# mini_metrix_clock.net
KiCad netlist of a schematic drawn in EAGLE
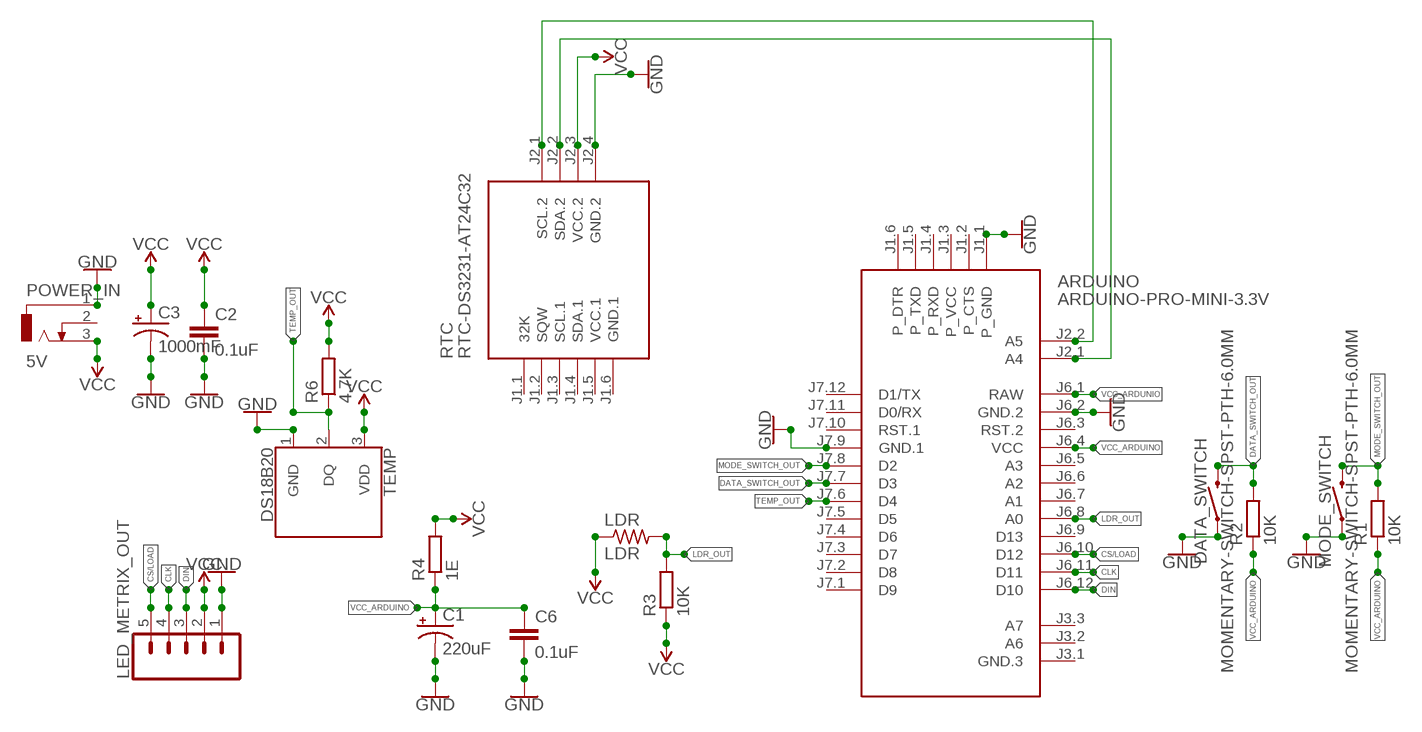
[diagram p0: schematic, sheet 1]

(export (version "E")
  (design (tool "Eeschema 10.0.6"))
  (components
    (comp (ref "ARDUINO")
      (value "ARDUINO-PRO-MINI-3.3V")
      (footprint "eagle-import:ARDUINO-PRO-MINI")
      (libsource (lib "eagle-import") (part "ARDUINO-PRO-MINI-3.3V"))
    )
    (comp (ref "C1")
      (value "220uF")
      (footprint "eagle-import:CPOL-RADIAL-2.5MM-6.5MM")
      (libsource (lib "eagle-import") (part "100UF-POLAR-RADIAL-2.5MM-25V-20%"))
    )
    (comp (ref "C2")
      (value "0.1uF")
      (footprint "eagle-import:CAP-PTH-SMALL-KIT")
      (libsource (lib "eagle-import") (part "0.1UF-KIT-EZ-50V-20%"))
    )
    (comp (ref "C3")
      (value "1000mF")
      (footprint "eagle-import:CPOL-RADIAL-5MM-10MM")
      (libsource (lib "eagle-import") (part "1000UF-RADIAL-5MM-25V-20%"))
    )
    (comp (ref "C6")
      (value "0.1uF")
      (footprint "eagle-import:CAP-PTH-SMALL-KIT")
      (libsource (lib "eagle-import") (part "0.1UF-KIT-EZ-50V-20%"))
    )
    (comp (ref "DATA_SWITCH")
      (value "MOMENTARY-SWITCH-SPST-PTH-6.0MM")
      (footprint "eagle-import:TACTILE_SWITCH_PTH_6.0MM")
      (libsource (lib "eagle-import") (part "MOMENTARY-SWITCH-SPST-PTH-6.0MM"))
    )
    (comp (ref "LDR")
      (value "LDR")
      (footprint "eagle-import:0204V")
      (libsource (lib "eagle-import") (part "R-US_0204/2V"))
    )
    (comp (ref "LED_METRIX_OUT")
      (value "CONN_05PTH_LONGPADS")
      (footprint "eagle-import:1X05_LONGPADS")
      (libsource (lib "eagle-import") (part "CONN_05PTH_LONGPADS"))
    )
    (comp (ref "MODE_SWITCH")
      (value "MOMENTARY-SWITCH-SPST-PTH-6.0MM")
      (footprint "eagle-import:TACTILE_SWITCH_PTH_6.0MM")
      (libsource (lib "eagle-import") (part "MOMENTARY-SWITCH-SPST-PTH-6.0MM"))
    )
    (comp (ref "POWER_IN")
      (value "5V")
      (footprint "eagle-import:DCJ0303")
      (libsource (lib "eagle-import") (part "DCJ0303"))
    )
    (comp (ref "R1")
      (value "10K")
      (footprint "eagle-import:0207_7")
      (libsource (lib "eagle-import") (part "R-EU_0207/7"))
    )
    (comp (ref "R2")
      (value "10K")
      (footprint "eagle-import:0207_7")
      (libsource (lib "eagle-import") (part "R-EU_0207/7"))
    )
    (comp (ref "R3")
      (value "10K")
      (footprint "eagle-import:0207_7")
      (libsource (lib "eagle-import") (part "R-EU_0207/7"))
    )
    (comp (ref "R4")
      (value "1E")
      (footprint "eagle-import:0207_7")
      (libsource (lib "eagle-import") (part "R-EU_0207/7"))
    )
    (comp (ref "R6")
      (value "4.7K")
      (footprint "eagle-import:0207_7")
      (libsource (lib "eagle-import") (part "R-EU_0207/7"))
    )
    (comp (ref "RTC")
      (value "RTC-DS3231-AT24C32")
      (footprint "eagle-import:RTC-DS3231-AT24C32")
      (libsource (lib "eagle-import") (part "RTC-DS3231-AT24C32"))
    )
    (comp (ref "TEMP")
      (value "DS18B20")
      (footprint "eagle-import:TO-92-AMMO")
      (libsource (lib "eagle-import") (part "DS18B20"))
    )
  )
  (nets
    (net (code "1") (name "/GND.1") (class "Default")
      (node (ref "RTC") (pin "J1.6") (pinfunction "GND.1_J1.6") (pintype "power_in"))
    )
    (net (code "2") (name "/VCC.1") (class "Default")
      (node (ref "RTC") (pin "J1.5") (pinfunction "VCC.1_J1.5") (pintype "power_in"))
    )
    (net (code "3") (name "CLK") (class "Default")
      (node (ref "ARDUINO") (pin "J6.11") (pinfunction "D11_J6.11") (pintype "bidirectional"))
      (node (ref "LED_METRIX_OUT") (pin "4") (pinfunction "4_4") (pintype "passive"))
    )
    (net (code "4") (name "CS{slash}LOAD") (class "Default")
      (node (ref "ARDUINO") (pin "J6.10") (pinfunction "D12_J6.10") (pintype "bidirectional"))
      (node (ref "LED_METRIX_OUT") (pin "5") (pinfunction "5_5") (pintype "passive"))
    )
    (net (code "5") (name "DATA_SWITCH_OUT") (class "Default")
      (node (ref "ARDUINO") (pin "J7.7") (pinfunction "D3_J7.7") (pintype "bidirectional"))
      (node (ref "DATA_SWITCH") (pin "3") (pinfunction "2_3") (pintype "passive"))
      (node (ref "R2") (pin "2") (pinfunction "2_2") (pintype "passive"))
    )
    (net (code "6") (name "DIN") (class "Default")
      (node (ref "ARDUINO") (pin "J6.12") (pinfunction "D10_J6.12") (pintype "bidirectional"))
      (node (ref "LED_METRIX_OUT") (pin "3") (pinfunction "3_3") (pintype "passive"))
    )
    (net (code "7") (name "GND") (class "Default")
      (node (ref "ARDUINO") (pin "J1.1") (pinfunction "P_GND_J1.1") (pintype "bidirectional"))
      (node (ref "ARDUINO") (pin "J6.2") (pinfunction "GND.2_J6.2") (pintype "power_in"))
      (node (ref "ARDUINO") (pin "J7.9") (pinfunction "GND.1_J7.9") (pintype "power_in"))
      (node (ref "C1") (pin "2") (pinfunction "-_2") (pintype "passive"))
      (node (ref "C2") (pin "2") (pinfunction "2_2") (pintype "passive"))
      (node (ref "C3") (pin "-") (pinfunction "-_-") (pintype "passive"))
      (node (ref "C6") (pin "2") (pinfunction "2_2") (pintype "passive"))
      (node (ref "DATA_SWITCH") (pin "1") (pinfunction "1_1") (pintype "passive"))
      (node (ref "LED_METRIX_OUT") (pin "1") (pinfunction "1_1") (pintype "passive"))
      (node (ref "MODE_SWITCH") (pin "1") (pinfunction "1_1") (pintype "passive"))
      (node (ref "POWER_IN") (pin "1") (pinfunction "1_1") (pintype "passive"))
      (node (ref "RTC") (pin "J2.4") (pinfunction "GND.2_J2.4") (pintype "power_in"))
      (node (ref "TEMP") (pin "1") (pinfunction "GND_1") (pintype "power_in"))
    )
    (net (code "8") (name "LDR_OUT") (class "Default")
      (node (ref "ARDUINO") (pin "J6.8") (pinfunction "A0_J6.8") (pintype "bidirectional"))
      (node (ref "LDR") (pin "2") (pinfunction "2_2") (pintype "passive"))
      (node (ref "R3") (pin "2") (pinfunction "2_2") (pintype "passive"))
    )
    (net (code "9") (name "MODE_SWITCH_OUT") (class "Default")
      (node (ref "ARDUINO") (pin "J7.8") (pinfunction "D2_J7.8") (pintype "bidirectional"))
      (node (ref "MODE_SWITCH") (pin "3") (pinfunction "2_3") (pintype "passive"))
      (node (ref "R1") (pin "2") (pinfunction "2_2") (pintype "passive"))
    )
    (net (code "10") (name "Net-(ARDUINO-A4)") (class "Default")
      (node (ref "ARDUINO") (pin "J2.1") (pinfunction "A4_J2.1") (pintype "bidirectional"))
      (node (ref "RTC") (pin "J2.2") (pinfunction "SDA.2_J2.2") (pintype "bidirectional"))
    )
    (net (code "11") (name "Net-(ARDUINO-A5)") (class "Default")
      (node (ref "ARDUINO") (pin "J2.2") (pinfunction "A5_J2.2") (pintype "bidirectional"))
      (node (ref "RTC") (pin "J2.1") (pinfunction "SCL.2_J2.1") (pintype "bidirectional"))
    )
    (net (code "12") (name "TEMP_OUT") (class "Default")
      (node (ref "ARDUINO") (pin "J7.6") (pinfunction "D4_J7.6") (pintype "bidirectional"))
      (node (ref "R6") (pin "1") (pinfunction "1_1") (pintype "passive"))
      (node (ref "TEMP") (pin "2") (pinfunction "DQ_2") (pintype "bidirectional"))
    )
    (net (code "13") (name "VCC") (class "Default")
      (node (ref "C2") (pin "1") (pinfunction "1_1") (pintype "passive"))
      (node (ref "C3") (pin "+") (pinfunction "+_+") (pintype "passive"))
      (node (ref "LDR") (pin "1") (pinfunction "1_1") (pintype "passive"))
      (node (ref "LED_METRIX_OUT") (pin "2") (pinfunction "2_2") (pintype "passive"))
      (node (ref "POWER_IN") (pin "3") (pinfunction "3_3") (pintype "passive"))
      (node (ref "R3") (pin "1") (pinfunction "1_1") (pintype "passive"))
      (node (ref "R4") (pin "2") (pinfunction "2_2") (pintype "passive"))
      (node (ref "R6") (pin "2") (pinfunction "2_2") (pintype "passive"))
      (node (ref "RTC") (pin "J2.3") (pinfunction "VCC.2_J2.3") (pintype "power_in"))
      (node (ref "TEMP") (pin "3") (pinfunction "VDD_3") (pintype "power_in"))
    )
    (net (code "14") (name "VCC_ARDUINO") (class "Default")
      (node (ref "ARDUINO") (pin "J6.4") (pinfunction "VCC_J6.4") (pintype "power_in"))
      (node (ref "C1") (pin "1") (pinfunction "+_1") (pintype "passive"))
      (node (ref "C6") (pin "1") (pinfunction "1_1") (pintype "passive"))
      (node (ref "R1") (pin "1") (pinfunction "1_1") (pintype "passive"))
      (node (ref "R2") (pin "1") (pinfunction "1_1") (pintype "passive"))
      (node (ref "R4") (pin "1") (pinfunction "1_1") (pintype "passive"))
    )
    (net (code "15") (name "VCC_ARDUNIO") (class "Default")
      (node (ref "ARDUINO") (pin "J6.1") (pinfunction "RAW_J6.1") (pintype "power_in"))
    )
    (net (code "16") (name "unconnected-(ARDUINO-A1-PadJ6.7)") (class "Default")
      (node (ref "ARDUINO") (pin "J6.7") (pinfunction "A1_J6.7") (pintype "bidirectional"))
    )
    (net (code "17") (name "unconnected-(ARDUINO-A2-PadJ6.6)") (class "Default")
      (node (ref "ARDUINO") (pin "J6.6") (pinfunction "A2_J6.6") (pintype "bidirectional"))
    )
    (net (code "18") (name "unconnected-(ARDUINO-A3-PadJ6.5)") (class "Default")
      (node (ref "ARDUINO") (pin "J6.5") (pinfunction "A3_J6.5") (pintype "bidirectional"))
    )
    (net (code "19") (name "unconnected-(ARDUINO-A6-PadJ3.2)") (class "Default")
      (node (ref "ARDUINO") (pin "J3.2") (pinfunction "A6_J3.2") (pintype "bidirectional"))
    )
    (net (code "20") (name "unconnected-(ARDUINO-A7-PadJ3.3)") (class "Default")
      (node (ref "ARDUINO") (pin "J3.3") (pinfunction "A7_J3.3") (pintype "bidirectional"))
    )
    (net (code "21") (name "unconnected-(ARDUINO-D0{slash}RX-PadJ7.11)") (class "Default")
      (node (ref "ARDUINO") (pin "J7.11") (pinfunction "D0/RX_J7.11") (pintype "bidirectional"))
    )
    (net (code "22") (name "unconnected-(ARDUINO-D1{slash}TX-PadJ7.12)") (class "Default")
      (node (ref "ARDUINO") (pin "J7.12") (pinfunction "D1/TX_J7.12") (pintype "bidirectional"))
    )
    (net (code "23") (name "unconnected-(ARDUINO-D5-PadJ7.5)") (class "Default")
      (node (ref "ARDUINO") (pin "J7.5") (pinfunction "D5_J7.5") (pintype "bidirectional"))
    )
    (net (code "24") (name "unconnected-(ARDUINO-D6-PadJ7.4)") (class "Default")
      (node (ref "ARDUINO") (pin "J7.4") (pinfunction "D6_J7.4") (pintype "bidirectional"))
    )
    (net (code "25") (name "unconnected-(ARDUINO-D7-PadJ7.3)") (class "Default")
      (node (ref "ARDUINO") (pin "J7.3") (pinfunction "D7_J7.3") (pintype "bidirectional"))
    )
    (net (code "26") (name "unconnected-(ARDUINO-D8-PadJ7.2)") (class "Default")
      (node (ref "ARDUINO") (pin "J7.2") (pinfunction "D8_J7.2") (pintype "bidirectional"))
    )
    (net (code "27") (name "unconnected-(ARDUINO-D9-PadJ7.1)") (class "Default")
      (node (ref "ARDUINO") (pin "J7.1") (pinfunction "D9_J7.1") (pintype "bidirectional"))
    )
    (net (code "28") (name "unconnected-(ARDUINO-D13-PadJ6.9)") (class "Default")
      (node (ref "ARDUINO") (pin "J6.9") (pinfunction "D13_J6.9") (pintype "bidirectional"))
    )
    (net (code "29") (name "unconnected-(ARDUINO-GND.3-PadJ3.1)") (class "Default")
      (node (ref "ARDUINO") (pin "J3.1") (pinfunction "GND.3_J3.1") (pintype "bidirectional"))
    )
    (net (code "30") (name "unconnected-(ARDUINO-P_CTS-PadJ1.2)") (class "Default")
      (node (ref "ARDUINO") (pin "J1.2") (pinfunction "P_CTS_J1.2") (pintype "bidirectional"))
    )
    (net (code "31") (name "unconnected-(ARDUINO-P_DTR-PadJ1.6)") (class "Default")
      (node (ref "ARDUINO") (pin "J1.6") (pinfunction "P_DTR_J1.6") (pintype "bidirectional"))
    )
    (net (code "32") (name "unconnected-(ARDUINO-P_RXD-PadJ1.4)") (class "Default")
      (node (ref "ARDUINO") (pin "J1.4") (pinfunction "P_RXD_J1.4") (pintype "bidirectional"))
    )
    (net (code "33") (name "unconnected-(ARDUINO-P_TXD-PadJ1.5)") (class "Default")
      (node (ref "ARDUINO") (pin "J1.5") (pinfunction "P_TXD_J1.5") (pintype "bidirectional"))
    )
    (net (code "34") (name "unconnected-(ARDUINO-P_VCC-PadJ1.3)") (class "Default")
      (node (ref "ARDUINO") (pin "J1.3") (pinfunction "P_VCC_J1.3") (pintype "bidirectional"))
    )
    (net (code "35") (name "unconnected-(ARDUINO-RST.1-PadJ7.10)") (class "Default")
      (node (ref "ARDUINO") (pin "J7.10") (pinfunction "RST.1_J7.10") (pintype "bidirectional"))
    )
    (net (code "36") (name "unconnected-(ARDUINO-RST.2-PadJ6.3)") (class "Default")
      (node (ref "ARDUINO") (pin "J6.3") (pinfunction "RST.2_J6.3") (pintype "bidirectional"))
    )
    (net (code "37") (name "unconnected-(POWER_IN-Pad2)") (class "Default")
      (node (ref "POWER_IN") (pin "2") (pinfunction "2_2") (pintype "passive"))
    )
    (net (code "38") (name "unconnected-(RTC-32K-PadJ1.1)") (class "Default")
      (node (ref "RTC") (pin "J1.1") (pinfunction "32K_J1.1") (pintype "bidirectional"))
    )
    (net (code "39") (name "unconnected-(RTC-SCL.1-PadJ1.3)") (class "Default")
      (node (ref "RTC") (pin "J1.3") (pinfunction "SCL.1_J1.3") (pintype "bidirectional"))
    )
    (net (code "40") (name "unconnected-(RTC-SDA.1-PadJ1.4)") (class "Default")
      (node (ref "RTC") (pin "J1.4") (pinfunction "SDA.1_J1.4") (pintype "bidirectional"))
    )
    (net (code "41") (name "unconnected-(RTC-SQW-PadJ1.2)") (class "Default")
      (node (ref "RTC") (pin "J1.2") (pinfunction "SQW_J1.2") (pintype "bidirectional"))
    )
  )
)
